# General_Overview.net
KiCad netlist of a schematic drawn in Altium Designer
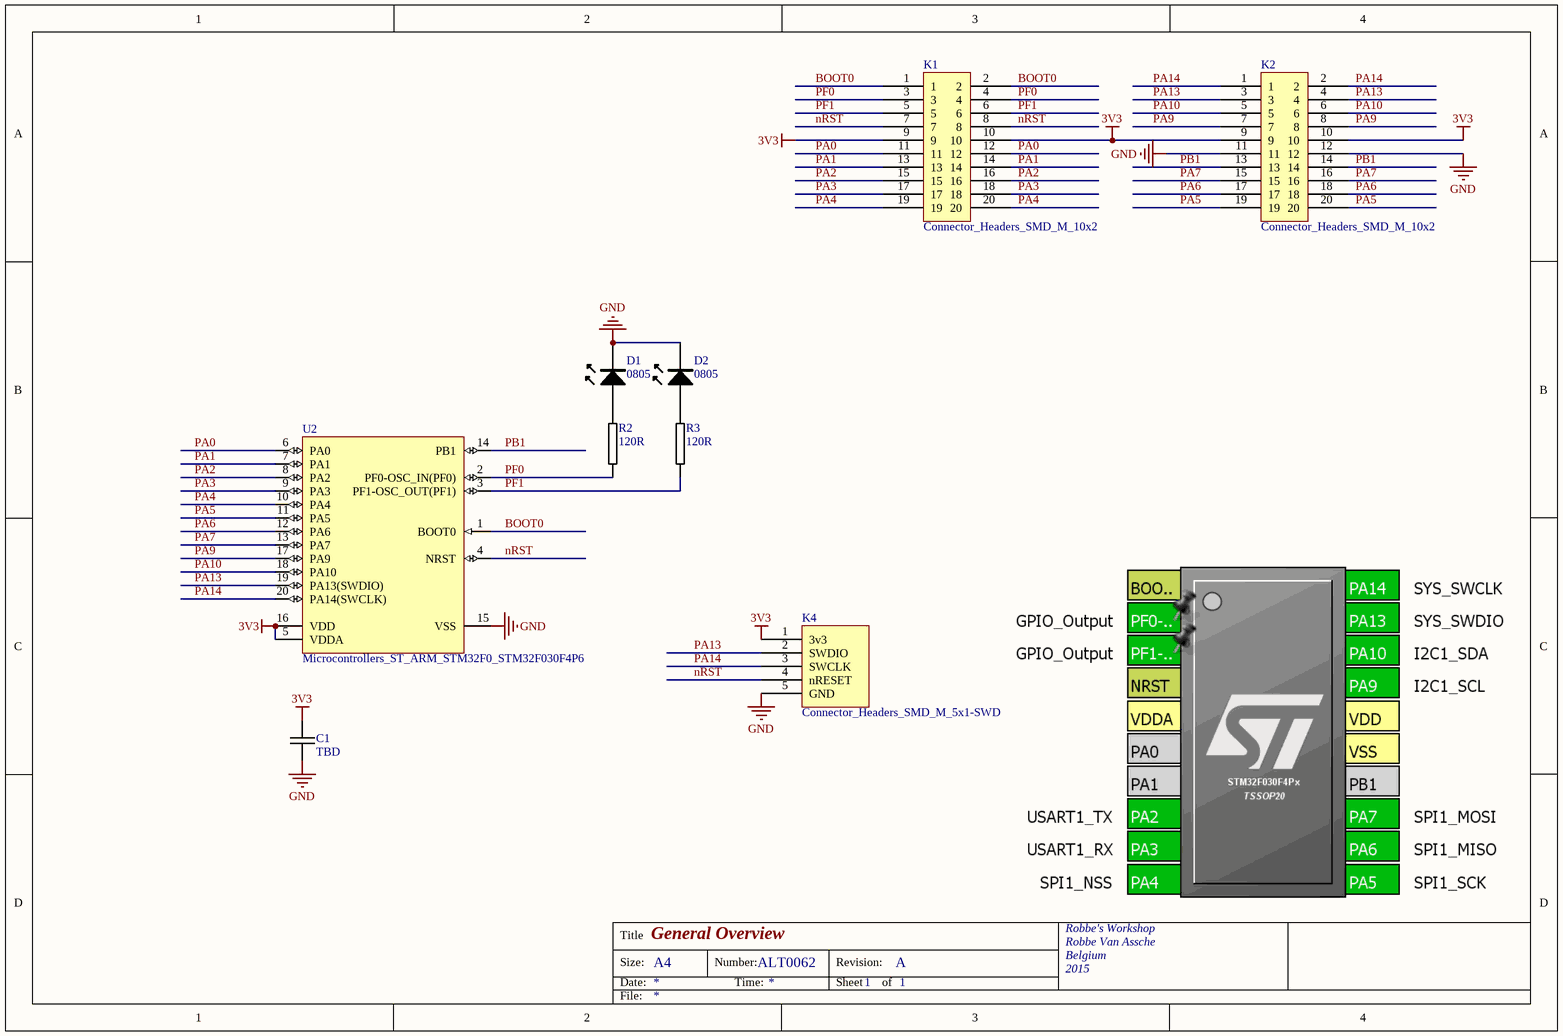
[diagram p0: General Overview.SchDoc]

(export (version "E")
  (design (tool "Eeschema 10.0.6"))
  (components
    (comp (ref "C1")
      (value "TBD")
      (footprint "1210C-GENERIC")
      (description "CAPACITOR 1210 CERAMIC VALUE TO BE DETERMINED")
      (libsource (lib "RVA_Altium_Library") (part "Passives_Capacitors_1210_1210C-TBD"))
    )
    (comp (ref "D1")
      (value "0805")
      (footprint "0805LED")
      (libsource (lib "RVA_Altium_Library") (part "LED_SMD_0805"))
    )
    (comp (ref "D2")
      (value "0805")
      (footprint "0805LED")
      (libsource (lib "RVA_Altium_Library") (part "LED_SMD_0805"))
    )
    (comp (ref "K1")
      (value "Connector_Headers_SMD_M_10x2")
      (footprint "Header_Male_2.54 10x2")
      (description "SMD Header 10x2")
      (libsource (lib "RVA_Altium_Library") (part "Connector_Headers_SMD_M_10x2"))
    )
    (comp (ref "K2")
      (value "Connector_Headers_SMD_M_10x2")
      (footprint "Header_Male_2.54 10x2")
      (description "SMD Header 10x2")
      (libsource (lib "RVA_Altium_Library") (part "Connector_Headers_SMD_M_10x2"))
    )
    (comp (ref "K4")
      (value "Connector_Headers_SMD_M_5x1-SWD")
      (footprint "Header_Male_2.54 5x1")
      (description "SWD SMD Header 5x1 for STM32")
      (libsource (lib "RVA_Altium_Library") (part "Connector_Headers_SMD_M_5x1-SWD"))
    )
    (comp (ref "R2")
      (value "120R")
      (footprint "0603R-120")
      (description "GENERIC RESISTOR 0603")
      (fields (field (name "TOLERANCE") "±1%") (field (name "MANUFACTURER PART NUMBER") "RMC 1/16 120 1% R"))
      (libsource (lib "RVA_Altium_Library") (part "0603R-120"))
    )
    (comp (ref "R3")
      (value "120R")
      (footprint "0603R-120")
      (description "GENERIC RESISTOR 0603")
      (fields (field (name "TOLERANCE") "±1%") (field (name "MANUFACTURER PART NUMBER") "RMC 1/16 120 1% R"))
      (libsource (lib "RVA_Altium_Library") (part "0603R-120"))
    )
    (comp (ref "U2")
      (value "Microcontrollers_ST_ARM_STM32F0_STM32F030F4P6")
      (footprint "STM-TSSOP20_N")
      (fields (field (name "PARTNUMBER") "STM32F030F4P6"))
      (libsource (lib "RVA_Altium_Library") (part "Microcontrollers_ST_ARM_STM32F0_STM32F030F4P6"))
    )
  )
  (nets
    (net (code "1") (name "/BOOT0") (class "Default")
      (node (ref "K1") (pin "1") (pinfunction "1_1") (pintype "passive"))
      (node (ref "K1") (pin "2") (pinfunction "2_2") (pintype "passive"))
      (node (ref "U2") (pin "1") (pinfunction "BOOT0_1") (pintype "input"))
    )
    (net (code "2") (name "/PA0") (class "Default")
      (node (ref "K1") (pin "11") (pinfunction "11_11") (pintype "passive"))
      (node (ref "K1") (pin "12") (pinfunction "12_12") (pintype "passive"))
      (node (ref "U2") (pin "6") (pinfunction "PA0_6") (pintype "bidirectional"))
    )
    (net (code "3") (name "/PA1") (class "Default")
      (node (ref "K1") (pin "13") (pinfunction "13_13") (pintype "passive"))
      (node (ref "K1") (pin "14") (pinfunction "14_14") (pintype "passive"))
      (node (ref "U2") (pin "7") (pinfunction "PA1_7") (pintype "bidirectional"))
    )
    (net (code "4") (name "/PA2") (class "Default")
      (node (ref "K1") (pin "15") (pinfunction "15_15") (pintype "passive"))
      (node (ref "K1") (pin "16") (pinfunction "16_16") (pintype "passive"))
      (node (ref "U2") (pin "8") (pinfunction "PA2_8") (pintype "bidirectional"))
    )
    (net (code "5") (name "/PA3") (class "Default")
      (node (ref "K1") (pin "17") (pinfunction "17_17") (pintype "passive"))
      (node (ref "K1") (pin "18") (pinfunction "18_18") (pintype "passive"))
      (node (ref "U2") (pin "9") (pinfunction "PA3_9") (pintype "bidirectional"))
    )
    (net (code "6") (name "/PA4") (class "Default")
      (node (ref "K1") (pin "19") (pinfunction "19_19") (pintype "passive"))
      (node (ref "K1") (pin "20") (pinfunction "20_20") (pintype "passive"))
      (node (ref "U2") (pin "10") (pinfunction "PA4_10") (pintype "bidirectional"))
    )
    (net (code "7") (name "/PA5") (class "Default")
      (node (ref "K2") (pin "19") (pinfunction "19_19") (pintype "passive"))
      (node (ref "K2") (pin "20") (pinfunction "20_20") (pintype "passive"))
      (node (ref "U2") (pin "11") (pinfunction "PA5_11") (pintype "bidirectional"))
    )
    (net (code "8") (name "/PA6") (class "Default")
      (node (ref "K2") (pin "17") (pinfunction "17_17") (pintype "passive"))
      (node (ref "K2") (pin "18") (pinfunction "18_18") (pintype "passive"))
      (node (ref "U2") (pin "12") (pinfunction "PA6_12") (pintype "bidirectional"))
    )
    (net (code "9") (name "/PA7") (class "Default")
      (node (ref "K2") (pin "15") (pinfunction "15_15") (pintype "passive"))
      (node (ref "K2") (pin "16") (pinfunction "16_16") (pintype "passive"))
      (node (ref "U2") (pin "13") (pinfunction "PA7_13") (pintype "bidirectional"))
    )
    (net (code "10") (name "/PA9") (class "Default")
      (node (ref "K2") (pin "7") (pinfunction "7_7") (pintype "passive"))
      (node (ref "K2") (pin "8") (pinfunction "8_8") (pintype "passive"))
      (node (ref "U2") (pin "17") (pinfunction "PA9_17") (pintype "bidirectional"))
    )
    (net (code "11") (name "/PA10") (class "Default")
      (node (ref "K2") (pin "5") (pinfunction "5_5") (pintype "passive"))
      (node (ref "K2") (pin "6") (pinfunction "6_6") (pintype "passive"))
      (node (ref "U2") (pin "18") (pinfunction "PA10_18") (pintype "bidirectional"))
    )
    (net (code "12") (name "/PA13") (class "Default")
      (node (ref "K2") (pin "3") (pinfunction "3_3") (pintype "passive"))
      (node (ref "K2") (pin "4") (pinfunction "4_4") (pintype "passive"))
      (node (ref "K4") (pin "2") (pinfunction "SWDIO_2") (pintype "passive"))
      (node (ref "U2") (pin "19") (pinfunction "PA13(SWDIO)_19") (pintype "bidirectional"))
    )
    (net (code "13") (name "/PA14") (class "Default")
      (node (ref "K2") (pin "1") (pinfunction "1_1") (pintype "passive"))
      (node (ref "K2") (pin "2") (pinfunction "2_2") (pintype "passive"))
      (node (ref "K4") (pin "3") (pinfunction "SWCLK_3") (pintype "passive"))
      (node (ref "U2") (pin "20") (pinfunction "PA14(SWCLK)_20") (pintype "bidirectional"))
    )
    (net (code "14") (name "/PB1") (class "Default")
      (node (ref "K2") (pin "13") (pinfunction "13_13") (pintype "passive"))
      (node (ref "K2") (pin "14") (pinfunction "14_14") (pintype "passive"))
      (node (ref "U2") (pin "14") (pinfunction "PB1_14") (pintype "bidirectional"))
    )
    (net (code "15") (name "/PF0") (class "Default")
      (node (ref "K1") (pin "3") (pinfunction "3_3") (pintype "passive"))
      (node (ref "K1") (pin "4") (pinfunction "4_4") (pintype "passive"))
      (node (ref "R2") (pin "1") (pintype "passive"))
      (node (ref "U2") (pin "2") (pinfunction "PF0-OSC_IN(PF0)_2") (pintype "bidirectional"))
    )
    (net (code "16") (name "/PF1") (class "Default")
      (node (ref "K1") (pin "5") (pinfunction "5_5") (pintype "passive"))
      (node (ref "K1") (pin "6") (pinfunction "6_6") (pintype "passive"))
      (node (ref "R3") (pin "1") (pintype "passive"))
      (node (ref "U2") (pin "3") (pinfunction "PF1-OSC_OUT(PF1)_3") (pintype "bidirectional"))
    )
    (net (code "17") (name "/nRST") (class "Default")
      (node (ref "K1") (pin "7") (pinfunction "7_7") (pintype "passive"))
      (node (ref "K1") (pin "8") (pinfunction "8_8") (pintype "passive"))
      (node (ref "K4") (pin "4") (pinfunction "nRESET_4") (pintype "passive"))
      (node (ref "U2") (pin "4") (pinfunction "NRST_4") (pintype "bidirectional"))
    )
    (net (code "18") (name "3V3") (class "Default")
      (node (ref "C1") (pin "1") (pintype "passive"))
      (node (ref "K1") (pin "10") (pinfunction "10_10") (pintype "passive"))
      (node (ref "K1") (pin "9") (pinfunction "9_9") (pintype "passive"))
      (node (ref "K2") (pin "10") (pinfunction "10_10") (pintype "passive"))
      (node (ref "K2") (pin "9") (pinfunction "9_9") (pintype "passive"))
      (node (ref "K4") (pin "1") (pinfunction "3v3_1") (pintype "passive"))
      (node (ref "U2") (pin "16") (pinfunction "VDD_16") (pintype "power_in"))
      (node (ref "U2") (pin "5") (pinfunction "VDDA_5") (pintype "power_in"))
    )
    (net (code "19") (name "GND") (class "Default")
      (node (ref "C1") (pin "2") (pintype "passive"))
      (node (ref "D1") (pin "K") (pintype "passive"))
      (node (ref "D2") (pin "K") (pintype "passive"))
      (node (ref "K2") (pin "11") (pinfunction "11_11") (pintype "passive"))
      (node (ref "K2") (pin "12") (pinfunction "12_12") (pintype "passive"))
      (node (ref "K4") (pin "5") (pinfunction "GND_5") (pintype "passive"))
      (node (ref "U2") (pin "15") (pinfunction "VSS_15") (pintype "power_in"))
    )
    (net (code "20") (name "Net-(D1-PadA)") (class "Default")
      (node (ref "D1") (pin "A") (pintype "passive"))
      (node (ref "R2") (pin "2") (pintype "passive"))
    )
    (net (code "21") (name "Net-(D2-PadA)") (class "Default")
      (node (ref "D2") (pin "A") (pintype "passive"))
      (node (ref "R3") (pin "2") (pintype "passive"))
    )
  )
)
